# SMD_Schaltplan.net
KiCad netlist of a schematic drawn in EAGLE
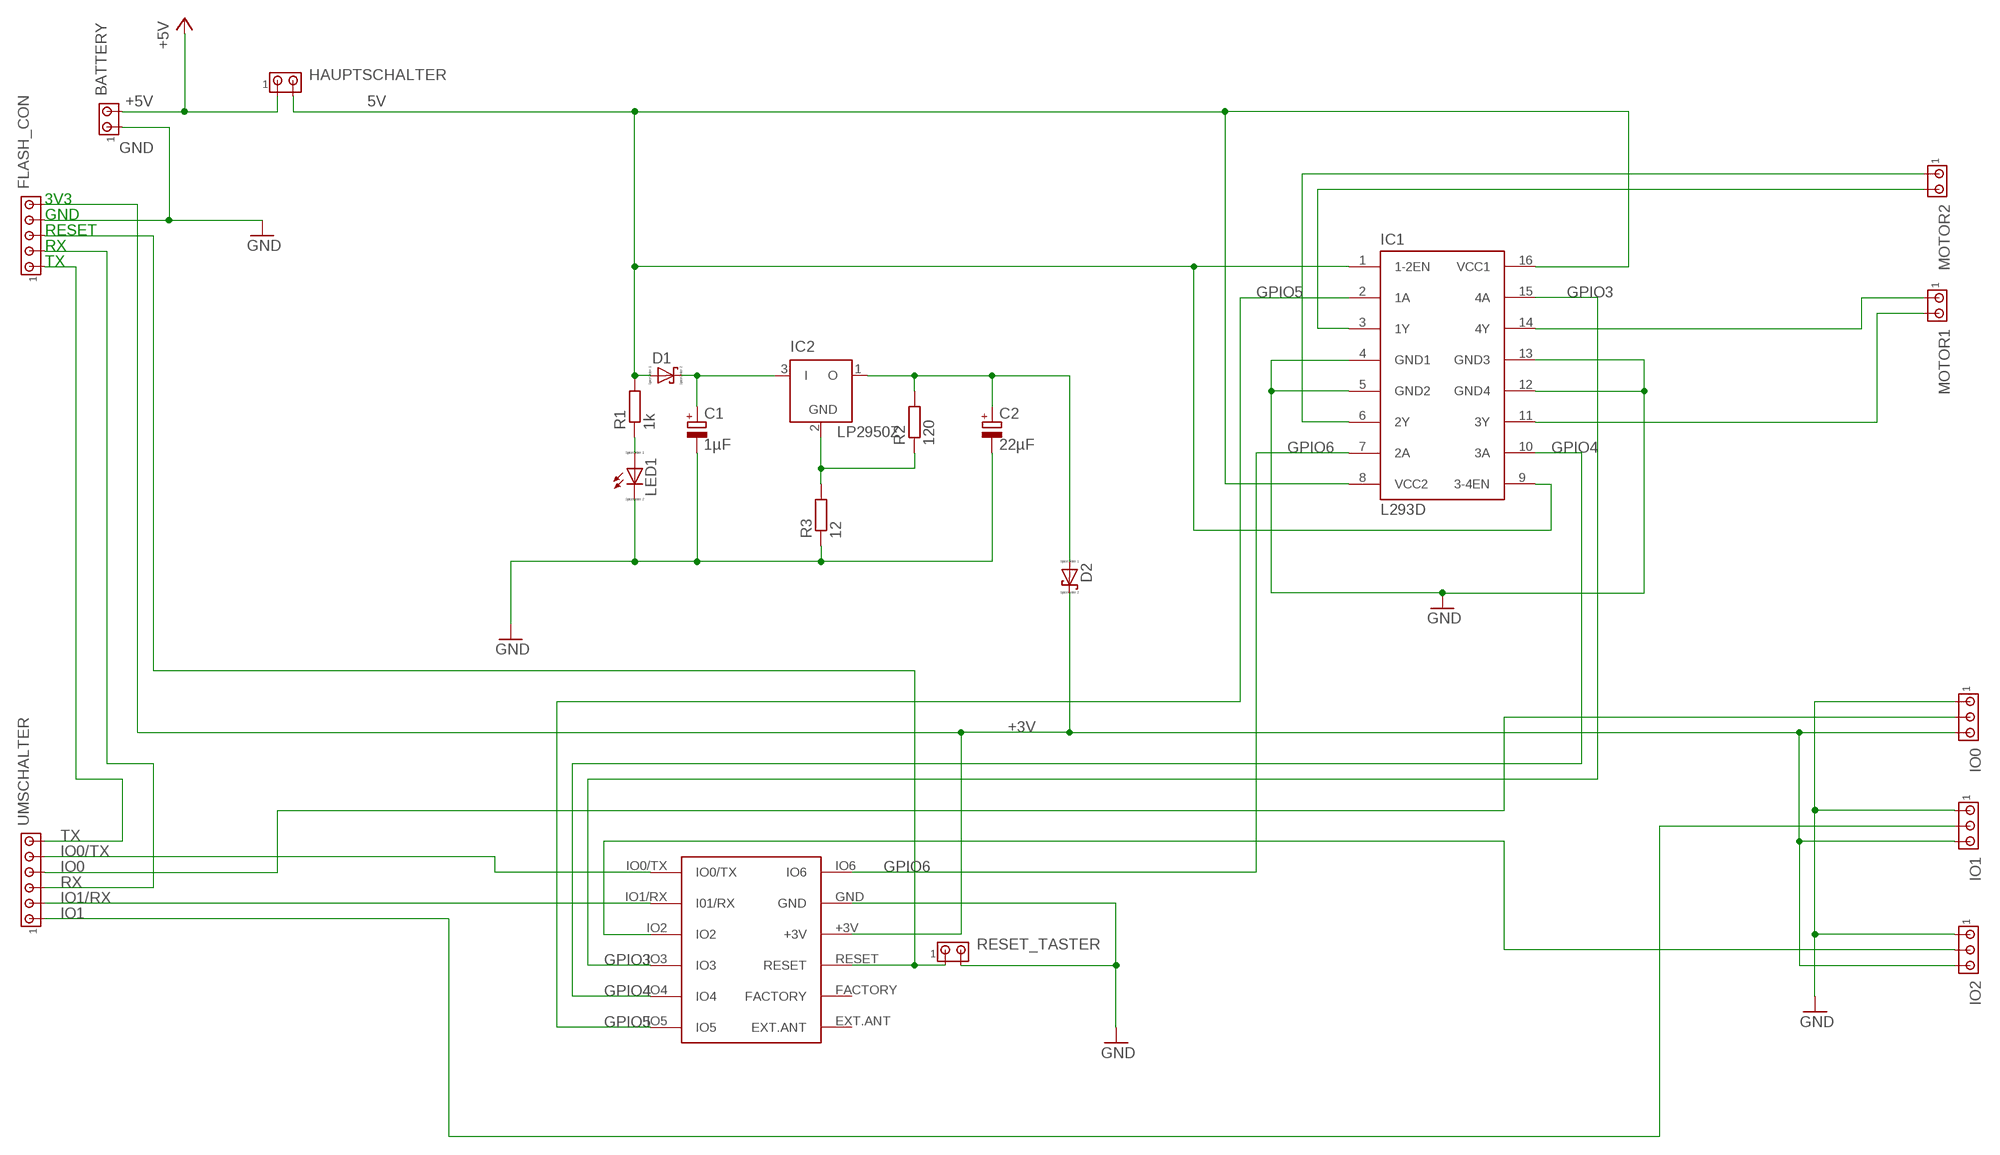
[diagram p0: schematic, sheet 1]

(export (version "E")
  (design (tool "Eeschema 10.0.6"))
  (components
    (comp (ref "BATTERY")
      (value "MTA02-100")
      (footprint "eagle-import:10X02MTA")
      (libsource (lib "eagle-import") (part "MTA02-100"))
    )
    (comp (ref "C1")
      (value "1µF")
      (footprint "eagle-import:E2,5-6E")
      (libsource (lib "eagle-import") (part "CPOL-EUE2,5-6E"))
    )
    (comp (ref "C2")
      (value "22µF")
      (footprint "eagle-import:E2,5-6E")
      (libsource (lib "eagle-import") (part "CPOL-EUE2,5-6E"))
    )
    (comp (ref "D1")
      (value "SCHOTTKY-DIODEDO35-7")
      (footprint "eagle-import:DIODE_DO35-7")
      (libsource (lib "eagle-import") (part "SCHOTTKY-DIODEDO35-7"))
    )
    (comp (ref "D2")
      (value "SCHOTTKY-DIODEDO35-7")
      (footprint "eagle-import:DIODE_DO35-7")
      (libsource (lib "eagle-import") (part "SCHOTTKY-DIODEDO35-7"))
    )
    (comp (ref "FLASH_CON")
      (value "MTA05-100")
      (footprint "eagle-import:10X05MTA")
      (libsource (lib "eagle-import") (part "MTA05-100"))
    )
    (comp (ref "HAUPTSCHALTER")
      (value "MTA02-100")
      (footprint "eagle-import:10X02MTA")
      (libsource (lib "eagle-import") (part "MTA02-100"))
    )
    (comp (ref "IC1")
      (value "L293D")
      (footprint "eagle-import:DIL16")
      (libsource (lib "eagle-import") (part "L293D"))
    )
    (comp (ref "IC2")
      (value "LP2950Z")
      (footprint "eagle-import:TO92")
      (libsource (lib "eagle-import") (part "LP2950Z"))
    )
    (comp (ref "IO0")
      (value "MTA03-100")
      (footprint "eagle-import:10X03MTA")
      (libsource (lib "eagle-import") (part "MTA03-100"))
    )
    (comp (ref "IO1")
      (value "MTA03-100")
      (footprint "eagle-import:10X03MTA")
      (libsource (lib "eagle-import") (part "MTA03-100"))
    )
    (comp (ref "IO2")
      (value "MTA03-100")
      (footprint "eagle-import:10X03MTA")
      (libsource (lib "eagle-import") (part "MTA03-100"))
    )
    (comp (ref "LED1")
      (value "LED_ELD260")
      (footprint "eagle-import:LED_LD260")
      (libsource (lib "eagle-import") (part "LED_ELD260"))
    )
    (comp (ref "MOTOR1")
      (value "MTA02-100")
      (footprint "eagle-import:10X02MTA")
      (libsource (lib "eagle-import") (part "MTA02-100"))
    )
    (comp (ref "MOTOR2")
      (value "MTA02-100")
      (footprint "eagle-import:10X02MTA")
      (libsource (lib "eagle-import") (part "MTA02-100"))
    )
    (comp (ref "R1")
      (value "1k")
      (footprint "eagle-import:0207_10")
      (libsource (lib "eagle-import") (part "resistor_R-EU_0207/10"))
    )
    (comp (ref "R2")
      (value "120")
      (footprint "eagle-import:0207_10")
      (libsource (lib "eagle-import") (part "R-EU_0207/10"))
    )
    (comp (ref "R3")
      (value "12")
      (footprint "eagle-import:0207_10")
      (libsource (lib "eagle-import") (part "R-EU_0207/10"))
    )
    (comp (ref "RESET_TASTER")
      (value "MTA02-100")
      (footprint "eagle-import:10X02MTA")
      (libsource (lib "eagle-import") (part "MTA02-100"))
    )
    (comp (ref "U$1")
      (value "SMD_RFDUINO")
      (footprint "eagle-import:RFDUINO_SMD")
      (libsource (lib "eagle-import") (part "SMD_RFDUINO"))
    )
    (comp (ref "UMSCHALTER")
      (value "MTA06-100")
      (footprint "eagle-import:10X06MTA")
      (libsource (lib "eagle-import") (part "MTA06-100"))
    )
  )
  (nets
    (net (code "1") (name "+5V") (class "Default")
      (node (ref "BATTERY") (pin "2") (pinfunction "2_2") (pintype "passive"))
      (node (ref "HAUPTSCHALTER") (pin "1") (pinfunction "1_1") (pintype "passive"))
    )
    (net (code "2") (name "/+3V") (class "Default")
      (node (ref "D2") (pin "C") (pinfunction "A_C") (pintype "passive"))
      (node (ref "FLASH_CON") (pin "5") (pinfunction "5_5") (pintype "passive"))
      (node (ref "IO0") (pin "3") (pinfunction "3_3") (pintype "passive"))
      (node (ref "IO1") (pin "3") (pinfunction "3_3") (pintype "passive"))
      (node (ref "IO2") (pin "3") (pinfunction "3_3") (pintype "passive"))
      (node (ref "U$1") (pin "+3V") (pinfunction "+3V_+3V") (pintype "power_in"))
    )
    (net (code "3") (name "/5V") (class "Default")
      (node (ref "D1") (pin "A") (pinfunction "C_A") (pintype "passive"))
      (node (ref "HAUPTSCHALTER") (pin "2") (pinfunction "2_2") (pintype "passive"))
      (node (ref "IC1") (pin "1") (pinfunction "1-2EN_1") (pintype "input"))
      (node (ref "IC1") (pin "16") (pinfunction "VCC1_16") (pintype "power_in"))
      (node (ref "IC1") (pin "8") (pinfunction "VCC2_8") (pintype "power_in"))
      (node (ref "IC1") (pin "9") (pinfunction "3-4EN_9") (pintype "input"))
      (node (ref "R1") (pin "2") (pinfunction "2_2") (pintype "passive"))
    )
    (net (code "4") (name "/GPIO3") (class "Default")
      (node (ref "IC1") (pin "15") (pinfunction "4A_15") (pintype "input"))
      (node (ref "U$1") (pin "IO3") (pinfunction "IO3_IO3") (pintype "bidirectional"))
    )
    (net (code "5") (name "/GPIO4") (class "Default")
      (node (ref "IC1") (pin "10") (pinfunction "3A_10") (pintype "input"))
      (node (ref "U$1") (pin "IO4") (pinfunction "IO4_IO4") (pintype "bidirectional"))
    )
    (net (code "6") (name "/GPIO5") (class "Default")
      (node (ref "IC1") (pin "2") (pinfunction "1A_2") (pintype "input"))
      (node (ref "U$1") (pin "IO5") (pinfunction "IO5_IO5") (pintype "bidirectional"))
    )
    (net (code "7") (name "/GPIO6") (class "Default")
      (node (ref "IC1") (pin "7") (pinfunction "2A_7") (pintype "input"))
      (node (ref "U$1") (pin "IO6") (pinfunction "IO6_IO6") (pintype "bidirectional"))
    )
    (net (code "8") (name "/IO0") (class "Default")
      (node (ref "IO0") (pin "2") (pinfunction "2_2") (pintype "passive"))
      (node (ref "UMSCHALTER") (pin "4") (pinfunction "4_4") (pintype "passive"))
    )
    (net (code "9") (name "/IO0{slash}TX") (class "Default")
      (node (ref "U$1") (pin "IO0/TX") (pinfunction "IO0/TX_IO0/TX") (pintype "bidirectional"))
      (node (ref "UMSCHALTER") (pin "5") (pinfunction "5_5") (pintype "passive"))
    )
    (net (code "10") (name "/IO1") (class "Default")
      (node (ref "IO1") (pin "2") (pinfunction "2_2") (pintype "passive"))
      (node (ref "UMSCHALTER") (pin "1") (pinfunction "1_1") (pintype "passive"))
    )
    (net (code "11") (name "/IO1{slash}RX") (class "Default")
      (node (ref "U$1") (pin "IO1/RX") (pinfunction "I01/RX_IO1/RX") (pintype "bidirectional"))
      (node (ref "UMSCHALTER") (pin "2") (pinfunction "2_2") (pintype "passive"))
    )
    (net (code "12") (name "/RX") (class "Default")
      (node (ref "FLASH_CON") (pin "2") (pinfunction "2_2") (pintype "passive"))
      (node (ref "UMSCHALTER") (pin "3") (pinfunction "3_3") (pintype "passive"))
    )
    (net (code "13") (name "/TX") (class "Default")
      (node (ref "FLASH_CON") (pin "1") (pinfunction "1_1") (pintype "passive"))
      (node (ref "UMSCHALTER") (pin "6") (pinfunction "6_6") (pintype "passive"))
    )
    (net (code "14") (name "GND") (class "Default")
      (node (ref "BATTERY") (pin "1") (pinfunction "1_1") (pintype "passive"))
      (node (ref "C1") (pin "-") (pinfunction "-_-") (pintype "passive"))
      (node (ref "C2") (pin "-") (pinfunction "-_-") (pintype "passive"))
      (node (ref "FLASH_CON") (pin "4") (pinfunction "4_4") (pintype "passive"))
      (node (ref "IC1") (pin "12") (pinfunction "GND4_12") (pintype "power_in"))
      (node (ref "IC1") (pin "13") (pinfunction "GND3_13") (pintype "power_in"))
      (node (ref "IC1") (pin "4") (pinfunction "GND1_4") (pintype "power_in"))
      (node (ref "IC1") (pin "5") (pinfunction "GND2_5") (pintype "power_in"))
      (node (ref "IO0") (pin "1") (pinfunction "1_1") (pintype "passive"))
      (node (ref "IO1") (pin "1") (pinfunction "1_1") (pintype "passive"))
      (node (ref "IO2") (pin "1") (pinfunction "1_1") (pintype "passive"))
      (node (ref "LED1") (pin "K") (pinfunction "C_K") (pintype "passive"))
      (node (ref "R3") (pin "1") (pinfunction "1_1") (pintype "passive"))
      (node (ref "RESET_TASTER") (pin "2") (pinfunction "2_2") (pintype "passive"))
      (node (ref "U$1") (pin "GND") (pinfunction "GND_GND") (pintype "power_in"))
    )
    (net (code "15") (name "Net-(D1-A)") (class "Default")
      (node (ref "C1") (pin "+") (pinfunction "+_+") (pintype "passive"))
      (node (ref "D1") (pin "C") (pinfunction "A_C") (pintype "passive"))
      (node (ref "IC2") (pin "3") (pinfunction "I_3") (pintype "input"))
    )
    (net (code "16") (name "Net-(D2-C)") (class "Default")
      (node (ref "C2") (pin "+") (pinfunction "+_+") (pintype "passive"))
      (node (ref "D2") (pin "A") (pinfunction "C_A") (pintype "passive"))
      (node (ref "IC2") (pin "1") (pinfunction "O_1") (pintype "input"))
      (node (ref "R2") (pin "2") (pinfunction "2_2") (pintype "passive"))
    )
    (net (code "17") (name "Net-(FLASH_CON-Pad3)") (class "Default")
      (node (ref "FLASH_CON") (pin "3") (pinfunction "3_3") (pintype "passive"))
      (node (ref "RESET_TASTER") (pin "1") (pinfunction "1_1") (pintype "passive"))
      (node (ref "U$1") (pin "RESET") (pinfunction "RESET_RESET") (pintype "input"))
    )
    (net (code "18") (name "Net-(IC1-1Y)") (class "Default")
      (node (ref "IC1") (pin "3") (pinfunction "1Y_3") (pintype "output"))
      (node (ref "MOTOR2") (pin "2") (pinfunction "2_2") (pintype "passive"))
    )
    (net (code "19") (name "Net-(IC1-2Y)") (class "Default")
      (node (ref "IC1") (pin "6") (pinfunction "2Y_6") (pintype "output"))
      (node (ref "MOTOR2") (pin "1") (pinfunction "1_1") (pintype "passive"))
    )
    (net (code "20") (name "Net-(IC1-3Y)") (class "Default")
      (node (ref "IC1") (pin "11") (pinfunction "3Y_11") (pintype "output"))
      (node (ref "MOTOR1") (pin "2") (pinfunction "2_2") (pintype "passive"))
    )
    (net (code "21") (name "Net-(IC1-4Y)") (class "Default")
      (node (ref "IC1") (pin "14") (pinfunction "4Y_14") (pintype "output"))
      (node (ref "MOTOR1") (pin "1") (pinfunction "1_1") (pintype "passive"))
    )
    (net (code "22") (name "Net-(IC2-GND)") (class "Default")
      (node (ref "IC2") (pin "2") (pinfunction "GND_2") (pintype "power_in"))
      (node (ref "R2") (pin "1") (pinfunction "1_1") (pintype "passive"))
      (node (ref "R3") (pin "2") (pinfunction "2_2") (pintype "passive"))
    )
    (net (code "23") (name "Net-(IO2-Pad2)") (class "Default")
      (node (ref "IO2") (pin "2") (pinfunction "2_2") (pintype "passive"))
      (node (ref "U$1") (pin "IO2") (pinfunction "IO2_IO2") (pintype "bidirectional"))
    )
    (net (code "24") (name "Net-(LED1-PadA)") (class "Default")
      (node (ref "LED1") (pin "A") (pinfunction "A_A") (pintype "passive"))
      (node (ref "R1") (pin "1") (pinfunction "1_1") (pintype "passive"))
    )
    (net (code "25") (name "unconnected-(U$1-PadEXT.ANT)") (class "Default")
      (node (ref "U$1") (pin "EXT.ANT") (pinfunction "EXT.ANT_EXT.ANT") (pintype "input"))
    )
    (net (code "26") (name "unconnected-(U$1-PadFACTORY)") (class "Default")
      (node (ref "U$1") (pin "FACTORY") (pinfunction "FACTORY_FACTORY") (pintype "input"))
    )
  )
)
